# Flash_Storage.net
KiCad netlist of a schematic drawn in Altium Designer
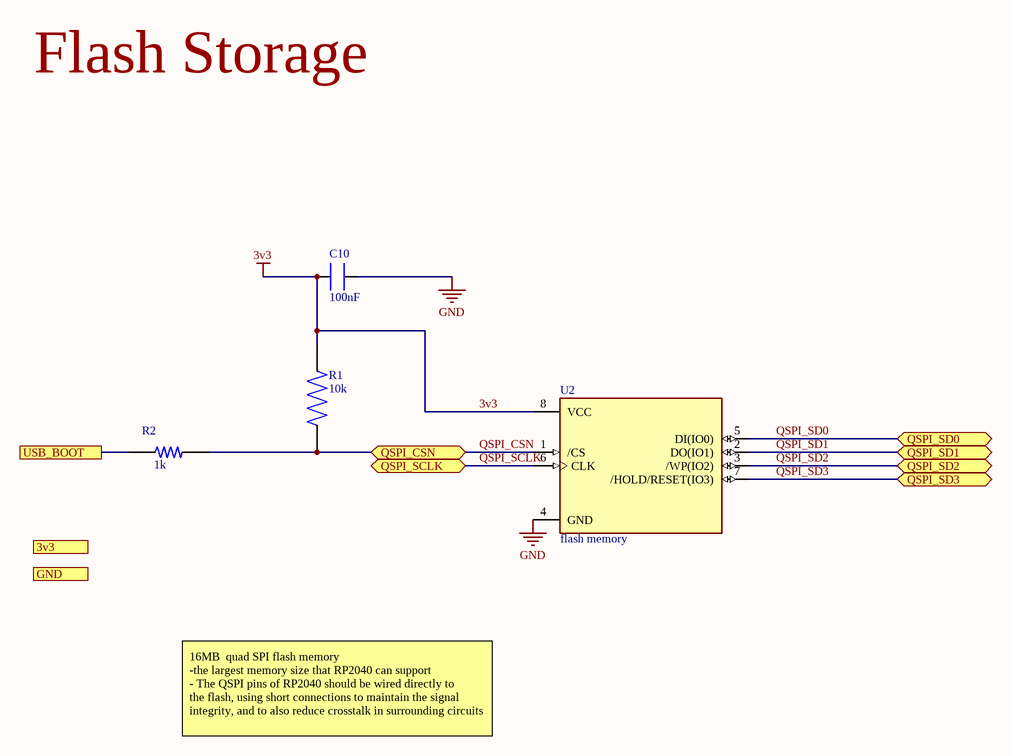
[diagram p0: Flash Storage.SchDoc]

(export (version "E")
  (design (tool "Eeschema 10.0.6"))
  (components
    (comp (ref "C10")
      (value "100nF")
      (footprint "CL10B104KB8NNNC")
      (description "SMD ceramic capacitor 0.1µF, tolerance ±10% 50V 0603 _1608 Metric_")
      (fields (field (name "MP") "CL10B104KB8NNNC") (field (name "MF") "Samsung Electro-Mechanics"))
      (libsource (lib "RP2040intLib") (part "CL10B104KB8NNNC"))
    )
    (comp (ref "R1")
      (value "10k")
      (footprint "RMCF0603JT10K0")
      (description "10 kOhms ±5% 0.1W, 1/10W Chip Resistor 0603 (1608 Metric) Automotive AEC-Q200 Thick Film")
      (fields (field (name "MP") "RMCF0603JT10K0"))
      (libsource (lib "RP2040intLib") (part "RMCF0603JT10K0"))
    )
    (comp (ref "R2")
      (value "1k")
      (footprint "RC0603FR-071KL")
      (description "1 kOhms ±1% 0.1W, 1/10W Chip Resistor 0603 (1608 Metric) Moisture Resistant Thick Film")
      (fields (field (name "MF") "Yageo") (field (name "MP") "RC0603FR-071KL"))
      (libsource (lib "RP2040intLib") (part "RC0603FR-071KL"))
    )
    (comp (ref "U2")
      (value "flash memory")
      (footprint "SOIC127P790X216-8N")
      (description "FLASH - NOR Memory IC 128Mb (16M x 8) SPI - Quad I/O, QPI, DTR 133 MHz 8-SOIC")
      (fields (field (name "MF") "Winbond Electronics") (field (name "MP") "W25Q128JVSIQ"))
      (libsource (lib "RP2040intLib") (part "W25Q128JVSIQ"))
    )
  )
  (nets
    (net (code "1") (name "/QSPI_CSN") (class "Default")
      (node (ref "R1") (pin "1") (pinfunction "1_1") (pintype "passive"))
      (node (ref "R2") (pin "2") (pinfunction "2_2") (pintype "passive"))
      (node (ref "U2") (pin "1") (pinfunction "/CS_1") (pintype "input"))
    )
    (net (code "2") (name "/QSPI_SCLK") (class "Default")
      (node (ref "U2") (pin "6") (pinfunction "CLK_6") (pintype "input"))
    )
    (net (code "3") (name "/QSPI_SD0") (class "Default")
      (node (ref "U2") (pin "5") (pinfunction "DI(IO0)_5") (pintype "bidirectional"))
    )
    (net (code "4") (name "/QSPI_SD1") (class "Default")
      (node (ref "U2") (pin "2") (pinfunction "DO(IO1)_2") (pintype "bidirectional"))
    )
    (net (code "5") (name "/QSPI_SD2") (class "Default")
      (node (ref "U2") (pin "3") (pinfunction "/WP(IO2)_3") (pintype "bidirectional"))
    )
    (net (code "6") (name "/QSPI_SD3") (class "Default")
      (node (ref "U2") (pin "7") (pinfunction "/HOLD/RESET(IO3)_7") (pintype "bidirectional"))
    )
    (net (code "7") (name "/USB_BOOT") (class "Default")
      (node (ref "R2") (pin "1") (pinfunction "1_1") (pintype "passive"))
    )
    (net (code "8") (name "3v3") (class "Default")
      (node (ref "C10") (pin "1") (pinfunction "1_1") (pintype "passive"))
      (node (ref "R1") (pin "2") (pinfunction "2_2") (pintype "passive"))
      (node (ref "U2") (pin "8") (pinfunction "VCC_8") (pintype "power_in"))
    )
    (net (code "9") (name "GND") (class "Default")
      (node (ref "C10") (pin "2") (pinfunction "2_2") (pintype "passive"))
      (node (ref "U2") (pin "4") (pinfunction "GND_4") (pintype "power_in"))
    )
  )
)
